# cansat_vehicle_v3_brd2.net
KiCad netlist of a schematic drawn in EAGLE
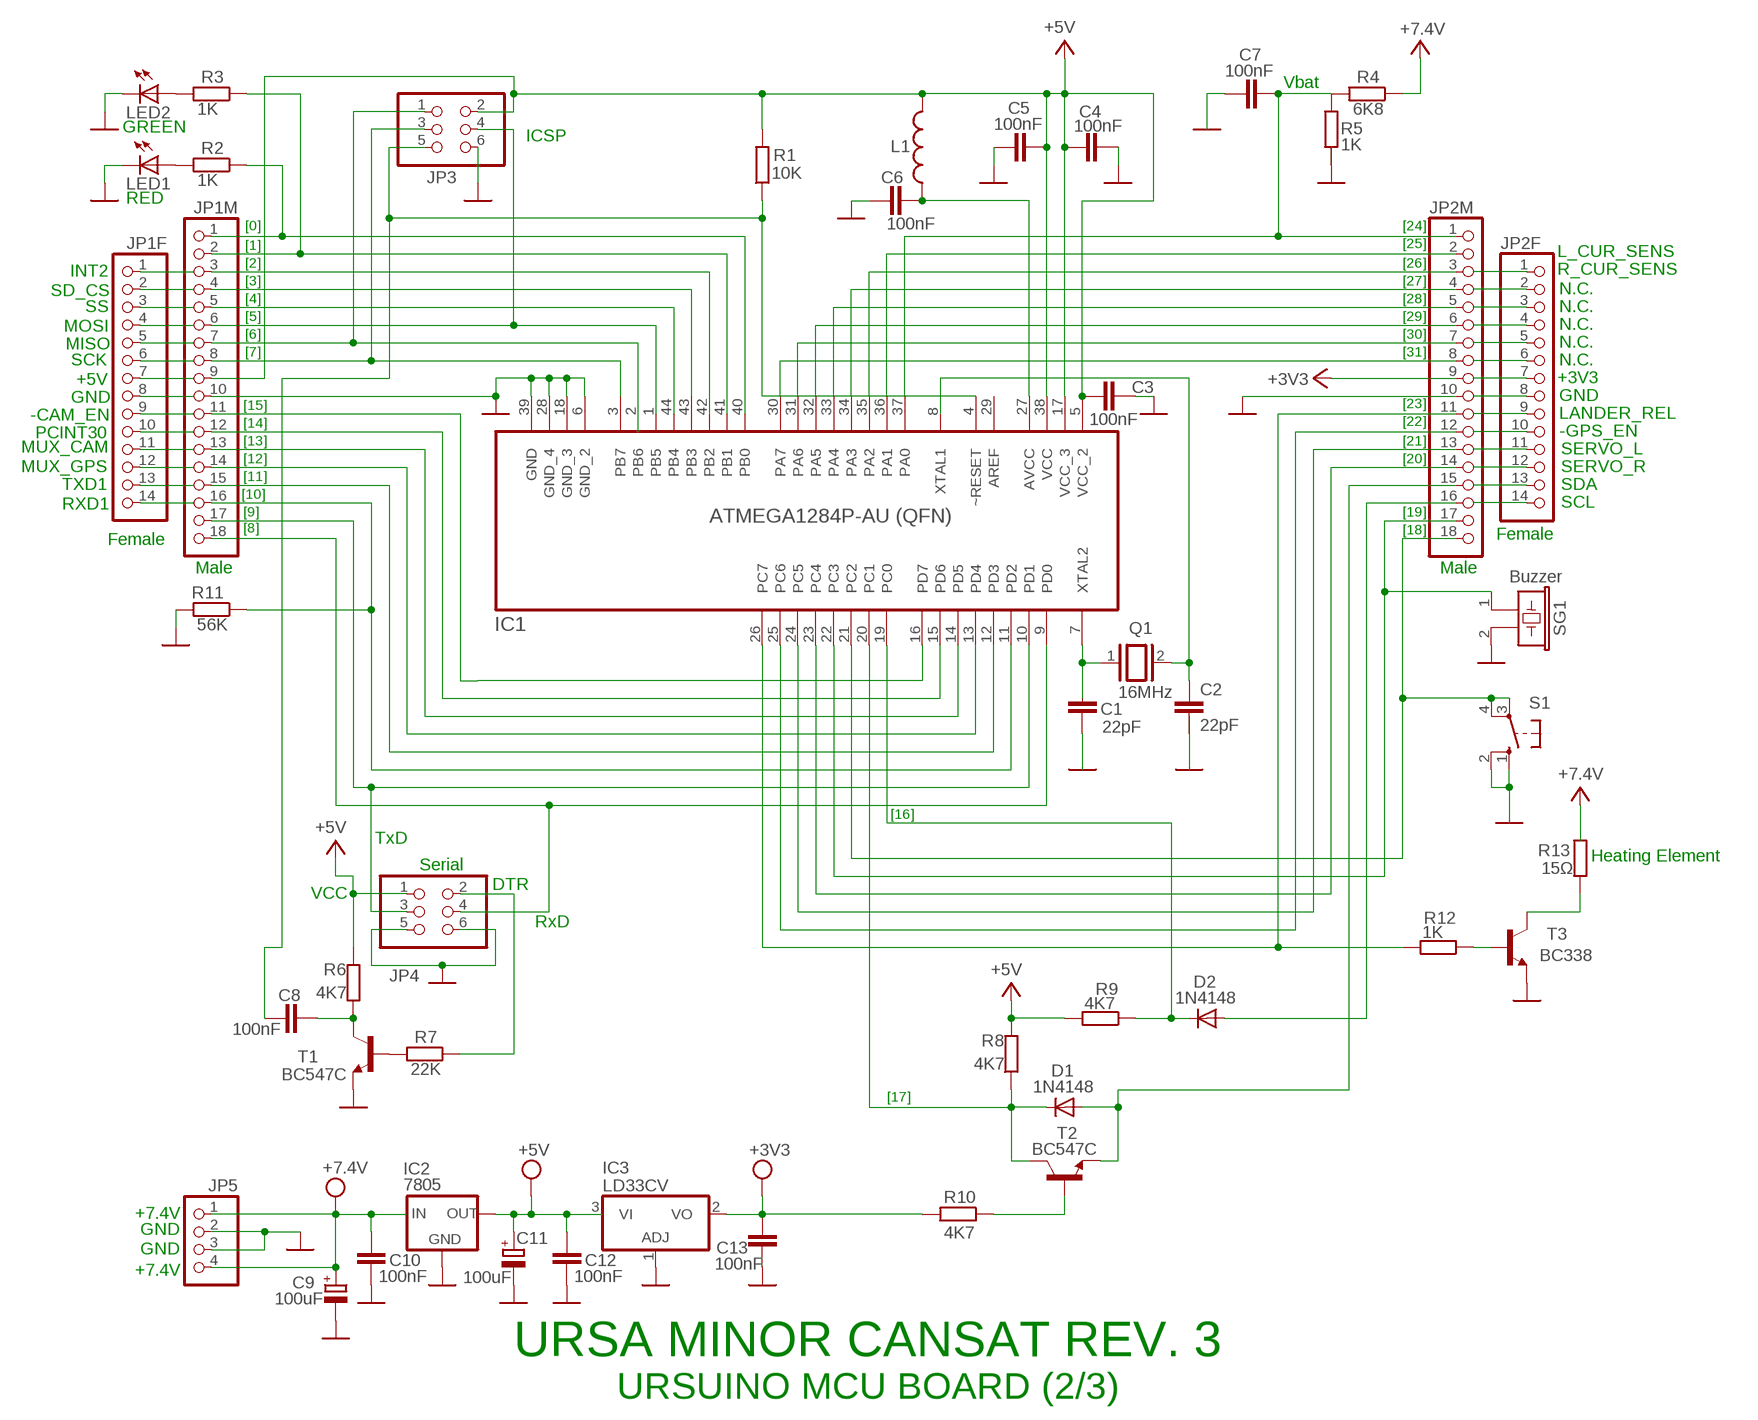
[diagram p0: schematic, sheet 1]

(export (version "E")
  (design (tool "Eeschema 10.0.6"))
  (components
    (comp (ref "C1")
      (value "22pF")
      (footprint "eagle-import:C2.5-2")
      (libsource (lib "eagle-import") (part "C2.5/2"))
    )
    (comp (ref "C2")
      (value "22pF")
      (footprint "eagle-import:C2.5-2")
      (libsource (lib "eagle-import") (part "C2.5/2"))
    )
    (comp (ref "C3")
      (value "100nF")
      (footprint "eagle-import:C2.5-2")
      (libsource (lib "eagle-import") (part "C2.5/2"))
    )
    (comp (ref "C4")
      (value "100nF")
      (footprint "eagle-import:C2.5-2")
      (libsource (lib "eagle-import") (part "C2.5/2"))
    )
    (comp (ref "C5")
      (value "100nF")
      (footprint "eagle-import:C2.5-2")
      (libsource (lib "eagle-import") (part "C2.5/2"))
    )
    (comp (ref "C6")
      (value "100nF")
      (footprint "eagle-import:C2.5-2")
      (libsource (lib "eagle-import") (part "C2.5/2"))
    )
    (comp (ref "C7")
      (value "100nF")
      (footprint "eagle-import:C2.5-2")
      (libsource (lib "eagle-import") (part "C2.5/2"))
    )
    (comp (ref "C8")
      (value "100nF")
      (footprint "eagle-import:C2.5-2")
      (libsource (lib "eagle-import") (part "C2.5/2"))
    )
    (comp (ref "C9")
      (value "100uF")
      (footprint "eagle-import:E2,5-7")
      (libsource (lib "eagle-import") (part "CPOL-EUE2.5-7"))
    )
    (comp (ref "C10")
      (value "100nF")
      (footprint "eagle-import:C2.5-2")
      (libsource (lib "eagle-import") (part "C2.5/2"))
    )
    (comp (ref "C11")
      (value "100uF")
      (footprint "eagle-import:E2,5-7")
      (libsource (lib "eagle-import") (part "CPOL-EUE2.5-7"))
    )
    (comp (ref "C12")
      (value "100nF")
      (footprint "eagle-import:C2.5-2")
      (libsource (lib "eagle-import") (part "C2.5/2"))
    )
    (comp (ref "C13")
      (value "100nF")
      (footprint "eagle-import:C2.5-2")
      (libsource (lib "eagle-import") (part "C2.5/2"))
    )
    (comp (ref "D1")
      (value "1N4148")
      (footprint "eagle-import:DO35-10")
      (libsource (lib "eagle-import") (part "1N4148DO35-10"))
    )
    (comp (ref "D2")
      (value "1N4148")
      (footprint "eagle-import:DO35-10")
      (libsource (lib "eagle-import") (part "1N4148DO35-10"))
    )
    (comp (ref "IC1")
      (value "ATMEGA1284P-AU (QFN)")
      (footprint "eagle-import:QFP80P1200X1200X120-44N")
      (fields (field (name "MPN") "ATMEGA1284P-AU"))
      (libsource (lib "eagle-import") (part "ATMEGA1284P-AU"))
    )
    (comp (ref "IC2")
      (value "7805")
      (footprint "eagle-import:78XXL")
      (libsource (lib "eagle-import") (part "78XXL"))
    )
    (comp (ref "IC3")
      (value "LD33CV")
      (footprint "eagle-import:TO220H")
      (libsource (lib "eagle-import") (part "317T"))
    )
    (comp (ref "JP1F")
      (value "PINHD-1X14")
      (footprint "eagle-import:1X14")
      (libsource (lib "eagle-import") (part "PINHD-1X14"))
    )
    (comp (ref "JP1M")
      (value "PINHD-1X18")
      (footprint "eagle-import:1X18")
      (libsource (lib "eagle-import") (part "PINHD-1X18"))
    )
    (comp (ref "JP2F")
      (value "PINHD-1X14")
      (footprint "eagle-import:1X14")
      (libsource (lib "eagle-import") (part "PINHD-1X14"))
    )
    (comp (ref "JP2M")
      (value "PINHD-1X18")
      (footprint "eagle-import:1X18")
      (libsource (lib "eagle-import") (part "PINHD-1X18"))
    )
    (comp (ref "JP3")
      (value "PINHD-2X3")
      (footprint "eagle-import:2X03")
      (libsource (lib "eagle-import") (part "PINHD-2X3"))
    )
    (comp (ref "JP4")
      (value "PINHD-2X3")
      (footprint "eagle-import:2X03")
      (libsource (lib "eagle-import") (part "PINHD-2X3"))
    )
    (comp (ref "JP5")
      (value "PINHD-1X4")
      (footprint "eagle-import:1X04")
      (libsource (lib "eagle-import") (part "PINHD-1X4"))
    )
    (comp (ref "L1")
      (value "L-US0204/5")
      (footprint "eagle-import:0204_5")
      (libsource (lib "eagle-import") (part "L-US0204/5"))
    )
    (comp (ref "LED1")
      (value "LED3MM")
      (footprint "eagle-import:LED3MM")
      (libsource (lib "eagle-import") (part "LED3MM"))
    )
    (comp (ref "LED2")
      (value "LED3MM")
      (footprint "eagle-import:LED3MM")
      (libsource (lib "eagle-import") (part "LED3MM"))
    )
    (comp (ref "Q1")
      (value "16MHz")
      (footprint "eagle-import:Q")
      (libsource (lib "eagle-import") (part "XTAL"))
    )
    (comp (ref "R1")
      (value "10K")
      (footprint "eagle-import:0204V")
      (libsource (lib "eagle-import") (part "R-EU_0204_2V"))
    )
    (comp (ref "R2")
      (value "1K")
      (footprint "eagle-import:0204V")
      (libsource (lib "eagle-import") (part "R-EU_0204_2V"))
    )
    (comp (ref "R3")
      (value "1K")
      (footprint "eagle-import:0204V")
      (libsource (lib "eagle-import") (part "R-EU_0204_2V"))
    )
    (comp (ref "R4")
      (value "6K8")
      (footprint "eagle-import:0204V")
      (libsource (lib "eagle-import") (part "R-EU_0204_2V"))
    )
    (comp (ref "R5")
      (value "1K")
      (footprint "eagle-import:0204V")
      (libsource (lib "eagle-import") (part "R-EU_0204_2V"))
    )
    (comp (ref "R6")
      (value "4K7")
      (footprint "eagle-import:0204V")
      (libsource (lib "eagle-import") (part "R-EU_0204_2V"))
    )
    (comp (ref "R7")
      (value "22K")
      (footprint "eagle-import:0204V")
      (libsource (lib "eagle-import") (part "R-EU_0204_2V"))
    )
    (comp (ref "R8")
      (value "4K7")
      (footprint "eagle-import:0204V")
      (libsource (lib "eagle-import") (part "R-EU_0204_2V"))
    )
    (comp (ref "R9")
      (value "4K7")
      (footprint "eagle-import:0204V")
      (libsource (lib "eagle-import") (part "R-EU_0204_2V"))
    )
    (comp (ref "R10")
      (value "4K7")
      (footprint "eagle-import:0204V")
      (libsource (lib "eagle-import") (part "R-EU_0204_2V"))
    )
    (comp (ref "R11")
      (value "56K")
      (footprint "eagle-import:0204V")
      (libsource (lib "eagle-import") (part "R-EU_0204_2V"))
    )
    (comp (ref "R12")
      (value "1K")
      (footprint "eagle-import:0204V")
      (libsource (lib "eagle-import") (part "R-EU_0204_2V"))
    )
    (comp (ref "R13")
      (value "15Ω")
      (footprint "eagle-import:0204V")
      (libsource (lib "eagle-import") (part "R-EU_0204_2V"))
    )
    (comp (ref "S1")
      (value "10-XX")
      (footprint "eagle-import:B3F-10XX")
      (fields (field (name "MPN") "B3F-1000"))
      (libsource (lib "eagle-import") (part "10-XX"))
    )
    (comp (ref "SG1")
      (value "Buzzer")
      (footprint "eagle-import:B_C11L")
      (libsource (lib "eagle-import") (part "B/C11L"))
    )
    (comp (ref "T1")
      (value "BC547C")
      (footprint "eagle-import:TO92-CBE")
      (libsource (lib "eagle-import") (part "-NPN-TO92-CBEBC547B"))
    )
    (comp (ref "T2")
      (value "BC547C")
      (footprint "eagle-import:TO92-CBE")
      (libsource (lib "eagle-import") (part "-NPN-TO92-CBEBC547B"))
    )
    (comp (ref "T3")
      (value "BC338")
      (footprint "eagle-import:TO92-CBE")
      (libsource (lib "eagle-import") (part "-NPN-TO92-CBEBC547B"))
    )
  )
  (nets
    (net (code "1") (name "+3V3") (class "Default")
      (node (ref "C10") (pin "1") (pinfunction "1_1") (pintype "passive"))
      (node (ref "C11") (pin "+") (pinfunction "+_+") (pintype "passive"))
      (node (ref "C12") (pin "1") (pinfunction "1_1") (pintype "passive"))
      (node (ref "C13") (pin "1") (pinfunction "1_1") (pintype "passive"))
      (node (ref "C3") (pin "1") (pinfunction "1_1") (pintype "passive"))
      (node (ref "C4") (pin "2") (pinfunction "2_2") (pintype "passive"))
      (node (ref "C5") (pin "1") (pinfunction "1_1") (pintype "passive"))
      (node (ref "C9") (pin "+") (pinfunction "+_+") (pintype "passive"))
      (node (ref "IC1") (pin "17") (pinfunction "VCC_3_17") (pintype "power_in"))
      (node (ref "IC1") (pin "38") (pinfunction "VCC_38") (pintype "power_in"))
      (node (ref "IC1") (pin "5") (pinfunction "VCC_2_5") (pintype "power_in"))
      (node (ref "IC2") (pin "IN") (pinfunction "IN_IN") (pintype "input"))
      (node (ref "IC2") (pin "OUT") (pinfunction "OUT_OUT") (pintype "passive"))
      (node (ref "IC3") (pin "2") (pinfunction "VO_2") (pintype "passive"))
      (node (ref "IC3") (pin "3") (pinfunction "VI_3") (pintype "input"))
      (node (ref "JP1M") (pin "9") (pinfunction "9_9") (pintype "passive"))
      (node (ref "JP2M") (pin "9") (pinfunction "9_9") (pintype "passive"))
      (node (ref "JP3") (pin "2") (pinfunction "2_2") (pintype "passive"))
      (node (ref "JP4") (pin "1") (pinfunction "1_1") (pintype "passive"))
      (node (ref "JP5") (pin "1") (pinfunction "1_1") (pintype "passive"))
      (node (ref "JP5") (pin "4") (pinfunction "4_4") (pintype "passive"))
      (node (ref "L1") (pin "2") (pinfunction "2_2") (pintype "passive"))
      (node (ref "R1") (pin "2") (pinfunction "2_2") (pintype "passive"))
      (node (ref "R10") (pin "2") (pinfunction "2_2") (pintype "passive"))
      (node (ref "R4") (pin "1") (pinfunction "1_1") (pintype "passive"))
      (node (ref "R6") (pin "2") (pinfunction "2_2") (pintype "passive"))
      (node (ref "R8") (pin "2") (pinfunction "2_2") (pintype "passive"))
      (node (ref "R9") (pin "2") (pinfunction "2_2") (pintype "passive"))
    )
    (net (code "2") (name "GND") (class "Default")
      (node (ref "C1") (pin "2") (pinfunction "2_2") (pintype "passive"))
      (node (ref "C10") (pin "2") (pinfunction "2_2") (pintype "passive"))
      (node (ref "C11") (pin "-") (pinfunction "-_-") (pintype "passive"))
      (node (ref "C12") (pin "2") (pinfunction "2_2") (pintype "passive"))
      (node (ref "C13") (pin "2") (pinfunction "2_2") (pintype "passive"))
      (node (ref "C2") (pin "2") (pinfunction "2_2") (pintype "passive"))
      (node (ref "C3") (pin "2") (pinfunction "2_2") (pintype "passive"))
      (node (ref "C4") (pin "1") (pinfunction "1_1") (pintype "passive"))
      (node (ref "C5") (pin "2") (pinfunction "2_2") (pintype "passive"))
      (node (ref "C6") (pin "1") (pinfunction "1_1") (pintype "passive"))
      (node (ref "C9") (pin "-") (pinfunction "-_-") (pintype "passive"))
      (node (ref "IC1") (pin "18") (pinfunction "GND_3_18") (pintype "passive"))
      (node (ref "IC1") (pin "28") (pinfunction "GND_4_28") (pintype "passive"))
      (node (ref "IC1") (pin "39") (pinfunction "GND_39") (pintype "passive"))
      (node (ref "IC1") (pin "6") (pinfunction "GND_2_6") (pintype "passive"))
      (node (ref "IC2") (pin "GND") (pinfunction "GND_GND") (pintype "input"))
      (node (ref "IC3") (pin "1") (pinfunction "ADJ_1") (pintype "input"))
      (node (ref "JP1M") (pin "10") (pinfunction "10_10") (pintype "passive"))
      (node (ref "JP2M") (pin "10") (pinfunction "10_10") (pintype "passive"))
      (node (ref "JP3") (pin "6") (pinfunction "6_6") (pintype "passive"))
      (node (ref "JP4") (pin "5") (pinfunction "5_5") (pintype "passive"))
      (node (ref "JP4") (pin "6") (pinfunction "6_6") (pintype "passive"))
      (node (ref "JP5") (pin "2") (pinfunction "2_2") (pintype "passive"))
      (node (ref "JP5") (pin "3") (pinfunction "3_3") (pintype "passive"))
      (node (ref "LED1") (pin "K") (pinfunction "C_K") (pintype "passive"))
      (node (ref "LED2") (pin "K") (pinfunction "C_K") (pintype "passive"))
      (node (ref "R11") (pin "2") (pinfunction "2_2") (pintype "passive"))
      (node (ref "R5") (pin "1") (pinfunction "1_1") (pintype "passive"))
      (node (ref "SG1") (pin "2") (pinfunction "2_2") (pintype "passive"))
      (node (ref "T1") (pin "E") (pinfunction "E_E") (pintype "passive"))
      (node (ref "T3") (pin "E") (pinfunction "E_E") (pintype "passive"))
    )
    (net (code "3") (name "Net-(C8-Pad2)") (class "Default")
      (node (ref "C8") (pin "2") (pinfunction "2_2") (pintype "passive"))
      (node (ref "R6") (pin "1") (pinfunction "1_1") (pintype "passive"))
      (node (ref "T1") (pin "C") (pinfunction "C_C") (pintype "passive"))
    )
    (net (code "4") (name "Net-(D1-PadA)") (class "Default")
      (node (ref "D1") (pin "A") (pinfunction "A_A") (pintype "passive"))
      (node (ref "JP2M") (pin "15") (pinfunction "15_15") (pintype "passive"))
      (node (ref "T2") (pin "E") (pinfunction "E_E") (pintype "passive"))
    )
    (net (code "5") (name "Net-(D2-PadA)") (class "Default")
      (node (ref "D2") (pin "A") (pinfunction "A_A") (pintype "passive"))
      (node (ref "JP2M") (pin "16") (pinfunction "16_16") (pintype "passive"))
    )
    (net (code "6") (name "Net-(IC1-AVCC)") (class "Default")
      (node (ref "C6") (pin "2") (pinfunction "2_2") (pintype "passive"))
      (node (ref "IC1") (pin "27") (pinfunction "AVCC_27") (pintype "power_in"))
      (node (ref "L1") (pin "1") (pinfunction "1_1") (pintype "passive"))
    )
    (net (code "7") (name "Net-(IC1-PA0)") (class "Default")
      (node (ref "C7") (pin "1") (pinfunction "1_1") (pintype "passive"))
      (node (ref "IC1") (pin "37") (pinfunction "PA0_37") (pintype "bidirectional"))
      (node (ref "JP2M") (pin "1") (pinfunction "1_1") (pintype "passive"))
      (node (ref "R4") (pin "2") (pinfunction "2_2") (pintype "passive"))
      (node (ref "R5") (pin "2") (pinfunction "2_2") (pintype "passive"))
    )
    (net (code "8") (name "Net-(IC1-PA1)") (class "Default")
      (node (ref "IC1") (pin "36") (pinfunction "PA1_36") (pintype "bidirectional"))
      (node (ref "JP2M") (pin "2") (pinfunction "2_2") (pintype "passive"))
    )
    (net (code "9") (name "Net-(IC1-PA2)") (class "Default")
      (node (ref "IC1") (pin "35") (pinfunction "PA2_35") (pintype "bidirectional"))
      (node (ref "JP2M") (pin "3") (pinfunction "3_3") (pintype "passive"))
    )
    (net (code "10") (name "Net-(IC1-PA3)") (class "Default")
      (node (ref "IC1") (pin "34") (pinfunction "PA3_34") (pintype "bidirectional"))
      (node (ref "JP2M") (pin "4") (pinfunction "4_4") (pintype "passive"))
    )
    (net (code "11") (name "Net-(IC1-PA4)") (class "Default")
      (node (ref "IC1") (pin "33") (pinfunction "PA4_33") (pintype "bidirectional"))
      (node (ref "JP2M") (pin "5") (pinfunction "5_5") (pintype "passive"))
    )
    (net (code "12") (name "Net-(IC1-PA5)") (class "Default")
      (node (ref "IC1") (pin "32") (pinfunction "PA5_32") (pintype "bidirectional"))
      (node (ref "JP2M") (pin "6") (pinfunction "6_6") (pintype "passive"))
    )
    (net (code "13") (name "Net-(IC1-PA6)") (class "Default")
      (node (ref "IC1") (pin "31") (pinfunction "PA6_31") (pintype "bidirectional"))
      (node (ref "JP2M") (pin "7") (pinfunction "7_7") (pintype "passive"))
    )
    (net (code "14") (name "Net-(IC1-PA7)") (class "Default")
      (node (ref "IC1") (pin "30") (pinfunction "PA7_30") (pintype "bidirectional"))
      (node (ref "JP2M") (pin "8") (pinfunction "8_8") (pintype "passive"))
    )
    (net (code "15") (name "Net-(IC1-PB0)") (class "Default")
      (node (ref "IC1") (pin "40") (pinfunction "PB0_40") (pintype "bidirectional"))
      (node (ref "JP1M") (pin "1") (pinfunction "1_1") (pintype "passive"))
      (node (ref "R2") (pin "1") (pinfunction "1_1") (pintype "passive"))
    )
    (net (code "16") (name "Net-(IC1-PB1)") (class "Default")
      (node (ref "IC1") (pin "41") (pinfunction "PB1_41") (pintype "bidirectional"))
      (node (ref "JP1M") (pin "2") (pinfunction "2_2") (pintype "passive"))
      (node (ref "R3") (pin "1") (pinfunction "1_1") (pintype "passive"))
    )
    (net (code "17") (name "Net-(IC1-PB2)") (class "Default")
      (node (ref "IC1") (pin "42") (pinfunction "PB2_42") (pintype "bidirectional"))
      (node (ref "JP1M") (pin "3") (pinfunction "3_3") (pintype "passive"))
    )
    (net (code "18") (name "Net-(IC1-PB3)") (class "Default")
      (node (ref "IC1") (pin "43") (pinfunction "PB3_43") (pintype "bidirectional"))
      (node (ref "JP1M") (pin "4") (pinfunction "4_4") (pintype "passive"))
    )
    (net (code "19") (name "Net-(IC1-PB4)") (class "Default")
      (node (ref "IC1") (pin "44") (pinfunction "PB4_44") (pintype "bidirectional"))
      (node (ref "JP1M") (pin "5") (pinfunction "5_5") (pintype "passive"))
    )
    (net (code "20") (name "Net-(IC1-PB5)") (class "Default")
      (node (ref "IC1") (pin "1") (pinfunction "PB5_1") (pintype "bidirectional"))
      (node (ref "JP1M") (pin "6") (pinfunction "6_6") (pintype "passive"))
      (node (ref "JP3") (pin "4") (pinfunction "4_4") (pintype "passive"))
    )
    (net (code "21") (name "Net-(IC1-PB6)") (class "Default")
      (node (ref "IC1") (pin "2") (pinfunction "PB6_2") (pintype "bidirectional"))
      (node (ref "JP1M") (pin "7") (pinfunction "7_7") (pintype "passive"))
      (node (ref "JP3") (pin "1") (pinfunction "1_1") (pintype "passive"))
    )
    (net (code "22") (name "Net-(IC1-PB7)") (class "Default")
      (node (ref "IC1") (pin "3") (pinfunction "PB7_3") (pintype "bidirectional"))
      (node (ref "JP1M") (pin "8") (pinfunction "8_8") (pintype "passive"))
      (node (ref "JP3") (pin "3") (pinfunction "3_3") (pintype "passive"))
    )
    (net (code "23") (name "Net-(IC1-PC0)") (class "Default")
      (node (ref "D2") (pin "C") (pinfunction "C_C") (pintype "passive"))
      (node (ref "IC1") (pin "19") (pinfunction "PC0_19") (pintype "bidirectional"))
      (node (ref "R9") (pin "1") (pinfunction "1_1") (pintype "passive"))
    )
    (net (code "24") (name "Net-(IC1-PC1)") (class "Default")
      (node (ref "D1") (pin "C") (pinfunction "C_C") (pintype "passive"))
      (node (ref "IC1") (pin "20") (pinfunction "PC1_20") (pintype "bidirectional"))
      (node (ref "R8") (pin "1") (pinfunction "1_1") (pintype "passive"))
      (node (ref "T2") (pin "C") (pinfunction "C_C") (pintype "passive"))
    )
    (net (code "25") (name "Net-(IC1-PC2)") (class "Default")
      (node (ref "IC1") (pin "21") (pinfunction "PC2_21") (pintype "bidirectional"))
      (node (ref "JP2M") (pin "18") (pinfunction "18_18") (pintype "passive"))
      (node (ref "S1") (pin "3") (pinfunction "P_3") (pintype "passive"))
      (node (ref "S1") (pin "4") (pinfunction "P1_4") (pintype "passive"))
    )
    (net (code "26") (name "Net-(IC1-PC3)") (class "Default")
      (node (ref "IC1") (pin "22") (pinfunction "PC3_22") (pintype "bidirectional"))
      (node (ref "JP2M") (pin "17") (pinfunction "17_17") (pintype "passive"))
      (node (ref "SG1") (pin "1") (pinfunction "1_1") (pintype "passive"))
    )
    (net (code "27") (name "Net-(IC1-PC4)") (class "Default")
      (node (ref "IC1") (pin "23") (pinfunction "PC4_23") (pintype "bidirectional"))
      (node (ref "JP2M") (pin "14") (pinfunction "14_14") (pintype "passive"))
    )
    (net (code "28") (name "Net-(IC1-PC5)") (class "Default")
      (node (ref "IC1") (pin "24") (pinfunction "PC5_24") (pintype "bidirectional"))
      (node (ref "JP2M") (pin "13") (pinfunction "13_13") (pintype "passive"))
    )
    (net (code "29") (name "Net-(IC1-PC6)") (class "Default")
      (node (ref "IC1") (pin "25") (pinfunction "PC6_25") (pintype "bidirectional"))
      (node (ref "JP2M") (pin "12") (pinfunction "12_12") (pintype "passive"))
    )
    (net (code "30") (name "Net-(IC1-PC7)") (class "Default")
      (node (ref "IC1") (pin "26") (pinfunction "PC7_26") (pintype "bidirectional"))
      (node (ref "JP2M") (pin "11") (pinfunction "11_11") (pintype "passive"))
      (node (ref "R12") (pin "2") (pinfunction "2_2") (pintype "passive"))
    )
    (net (code "31") (name "Net-(IC1-PD0)") (class "Default")
      (node (ref "IC1") (pin "9") (pinfunction "PD0_9") (pintype "bidirectional"))
      (node (ref "JP1M") (pin "18") (pinfunction "18_18") (pintype "passive"))
      (node (ref "JP4") (pin "4") (pinfunction "4_4") (pintype "passive"))
    )
    (net (code "32") (name "Net-(IC1-PD1)") (class "Default")
      (node (ref "IC1") (pin "10") (pinfunction "PD1_10") (pintype "bidirectional"))
      (node (ref "JP1M") (pin "17") (pinfunction "17_17") (pintype "passive"))
      (node (ref "JP4") (pin "3") (pinfunction "3_3") (pintype "passive"))
    )
    (net (code "33") (name "Net-(IC1-PD2)") (class "Default")
      (node (ref "IC1") (pin "11") (pinfunction "PD2_11") (pintype "bidirectional"))
      (node (ref "JP1M") (pin "16") (pinfunction "16_16") (pintype "passive"))
      (node (ref "R11") (pin "1") (pinfunction "1_1") (pintype "passive"))
    )
    (net (code "34") (name "Net-(IC1-PD3)") (class "Default")
      (node (ref "IC1") (pin "12") (pinfunction "PD3_12") (pintype "bidirectional"))
      (node (ref "JP1M") (pin "15") (pinfunction "15_15") (pintype "passive"))
    )
    (net (code "35") (name "Net-(IC1-PD4)") (class "Default")
      (node (ref "IC1") (pin "13") (pinfunction "PD4_13") (pintype "bidirectional"))
      (node (ref "JP1M") (pin "14") (pinfunction "14_14") (pintype "passive"))
    )
    (net (code "36") (name "Net-(IC1-PD5)") (class "Default")
      (node (ref "IC1") (pin "14") (pinfunction "PD5_14") (pintype "bidirectional"))
      (node (ref "JP1M") (pin "13") (pinfunction "13_13") (pintype "passive"))
    )
    (net (code "37") (name "Net-(IC1-PD6)") (class "Default")
      (node (ref "IC1") (pin "15") (pinfunction "PD6_15") (pintype "bidirectional"))
      (node (ref "JP1M") (pin "12") (pinfunction "12_12") (pintype "passive"))
    )
    (net (code "38") (name "Net-(IC1-PD7)") (class "Default")
      (node (ref "IC1") (pin "16") (pinfunction "PD7_16") (pintype "bidirectional"))
      (node (ref "JP1M") (pin "11") (pinfunction "11_11") (pintype "passive"))
    )
    (net (code "39") (name "Net-(IC1-XTAL1)") (class "Default")
      (node (ref "C2") (pin "1") (pinfunction "1_1") (pintype "passive"))
      (node (ref "IC1") (pin "8") (pinfunction "XTAL1_8") (pintype "input"))
      (node (ref "Q1") (pin "2") (pinfunction "2_2") (pintype "passive"))
    )
    (net (code "40") (name "Net-(IC1-XTAL2)") (class "Default")
      (node (ref "C1") (pin "1") (pinfunction "1_1") (pintype "passive"))
      (node (ref "IC1") (pin "7") (pinfunction "XTAL2_7") (pintype "output"))
      (node (ref "Q1") (pin "1") (pinfunction "1_1") (pintype "passive"))
    )
    (net (code "41") (name "Net-(IC1-~{RESET})") (class "Default")
      (node (ref "C8") (pin "1") (pinfunction "1_1") (pintype "passive"))
      (node (ref "IC1") (pin "4") (pinfunction "~{RESET}_4") (pintype "input"))
      (node (ref "JP3") (pin "5") (pinfunction "5_5") (pintype "passive"))
      (node (ref "R1") (pin "1") (pinfunction "1_1") (pintype "passive"))
    )
    (net (code "42") (name "Net-(JP4-Pad2)") (class "Default")
      (node (ref "JP4") (pin "2") (pinfunction "2_2") (pintype "passive"))
      (node (ref "R7") (pin "1") (pinfunction "1_1") (pintype "passive"))
    )
    (net (code "43") (name "Net-(LED1-PadA)") (class "Default")
      (node (ref "LED1") (pin "A") (pinfunction "A_A") (pintype "passive"))
      (node (ref "R2") (pin "2") (pinfunction "2_2") (pintype "passive"))
    )
    (net (code "44") (name "Net-(LED2-PadA)") (class "Default")
      (node (ref "LED2") (pin "A") (pinfunction "A_A") (pintype "passive"))
      (node (ref "R3") (pin "2") (pinfunction "2_2") (pintype "passive"))
    )
    (net (code "45") (name "Net-(R7-Pad2)") (class "Default")
      (node (ref "R7") (pin "2") (pinfunction "2_2") (pintype "passive"))
      (node (ref "T1") (pin "B") (pinfunction "B_B") (pintype "passive"))
    )
    (net (code "46") (name "Net-(R10-Pad1)") (class "Default")
      (node (ref "R10") (pin "1") (pinfunction "1_1") (pintype "passive"))
      (node (ref "T2") (pin "B") (pinfunction "B_B") (pintype "passive"))
    )
    (net (code "47") (name "Net-(R12-Pad1)") (class "Default")
      (node (ref "R12") (pin "1") (pinfunction "1_1") (pintype "passive"))
      (node (ref "T3") (pin "B") (pinfunction "B_B") (pintype "passive"))
    )
    (net (code "48") (name "Net-(R13-Pad1)") (class "Default")
      (node (ref "R13") (pin "1") (pinfunction "1_1") (pintype "passive"))
      (node (ref "T3") (pin "C") (pinfunction "C_C") (pintype "passive"))
    )
    (net (code "49") (name "Net-(S1-S)") (class "Default")
      (node (ref "S1") (pin "1") (pinfunction "S_1") (pintype "passive"))
      (node (ref "S1") (pin "2") (pinfunction "S1_2") (pintype "passive"))
    )
    (net (code "50") (name "unconnected-(C7-Pad2)") (class "Default")
      (node (ref "C7") (pin "2") (pinfunction "2_2") (pintype "passive"))
    )
    (net (code "51") (name "unconnected-(IC1-AREF-Pad29)") (class "Default")
      (node (ref "IC1") (pin "29") (pinfunction "AREF_29") (pintype "input"))
    )
    (net (code "52") (name "unconnected-(JP1F-Pad1)") (class "Default")
      (node (ref "JP1F") (pin "1") (pinfunction "1_1") (pintype "passive"))
    )
    (net (code "53") (name "unconnected-(JP1F-Pad2)") (class "Default")
      (node (ref "JP1F") (pin "2") (pinfunction "2_2") (pintype "passive"))
    )
    (net (code "54") (name "unconnected-(JP1F-Pad3)") (class "Default")
      (node (ref "JP1F") (pin "3") (pinfunction "3_3") (pintype "passive"))
    )
    (net (code "55") (name "unconnected-(JP1F-Pad4)") (class "Default")
      (node (ref "JP1F") (pin "4") (pinfunction "4_4") (pintype "passive"))
    )
    (net (code "56") (name "unconnected-(JP1F-Pad5)") (class "Default")
      (node (ref "JP1F") (pin "5") (pinfunction "5_5") (pintype "passive"))
    )
    (net (code "57") (name "unconnected-(JP1F-Pad6)") (class "Default")
      (node (ref "JP1F") (pin "6") (pinfunction "6_6") (pintype "passive"))
    )
    (net (code "58") (name "unconnected-(JP1F-Pad7)") (class "Default")
      (node (ref "JP1F") (pin "7") (pinfunction "7_7") (pintype "passive"))
    )
    (net (code "59") (name "unconnected-(JP1F-Pad8)") (class "Default")
      (node (ref "JP1F") (pin "8") (pinfunction "8_8") (pintype "passive"))
    )
    (net (code "60") (name "unconnected-(JP1F-Pad9)") (class "Default")
      (node (ref "JP1F") (pin "9") (pinfunction "9_9") (pintype "passive"))
    )
    (net (code "61") (name "unconnected-(JP1F-Pad10)") (class "Default")
      (node (ref "JP1F") (pin "10") (pinfunction "10_10") (pintype "passive"))
    )
    (net (code "62") (name "unconnected-(JP1F-Pad11)") (class "Default")
      (node (ref "JP1F") (pin "11") (pinfunction "11_11") (pintype "passive"))
    )
    (net (code "63") (name "unconnected-(JP1F-Pad12)") (class "Default")
      (node (ref "JP1F") (pin "12") (pinfunction "12_12") (pintype "passive"))
    )
    (net (code "64") (name "unconnected-(JP1F-Pad13)") (class "Default")
      (node (ref "JP1F") (pin "13") (pinfunction "13_13") (pintype "passive"))
    )
    (net (code "65") (name "unconnected-(JP1F-Pad14)") (class "Default")
      (node (ref "JP1F") (pin "14") (pinfunction "14_14") (pintype "passive"))
    )
    (net (code "66") (name "unconnected-(JP2F-Pad1)") (class "Default")
      (node (ref "JP2F") (pin "1") (pinfunction "1_1") (pintype "passive"))
    )
    (net (code "67") (name "unconnected-(JP2F-Pad2)") (class "Default")
      (node (ref "JP2F") (pin "2") (pinfunction "2_2") (pintype "passive"))
    )
    (net (code "68") (name "unconnected-(JP2F-Pad3)") (class "Default")
      (node (ref "JP2F") (pin "3") (pinfunction "3_3") (pintype "passive"))
    )
    (net (code "69") (name "unconnected-(JP2F-Pad4)") (class "Default")
      (node (ref "JP2F") (pin "4") (pinfunction "4_4") (pintype "passive"))
    )
    (net (code "70") (name "unconnected-(JP2F-Pad5)") (class "Default")
      (node (ref "JP2F") (pin "5") (pinfunction "5_5") (pintype "passive"))
    )
    (net (code "71") (name "unconnected-(JP2F-Pad6)") (class "Default")
      (node (ref "JP2F") (pin "6") (pinfunction "6_6") (pintype "passive"))
    )
    (net (code "72") (name "unconnected-(JP2F-Pad7)") (class "Default")
      (node (ref "JP2F") (pin "7") (pinfunction "7_7") (pintype "passive"))
    )
    (net (code "73") (name "unconnected-(JP2F-Pad8)") (class "Default")
      (node (ref "JP2F") (pin "8") (pinfunction "8_8") (pintype "passive"))
    )
    (net (code "74") (name "unconnected-(JP2F-Pad9)") (class "Default")
      (node (ref "JP2F") (pin "9") (pinfunction "9_9") (pintype "passive"))
    )
    (net (code "75") (name "unconnected-(JP2F-Pad10)") (class "Default")
      (node (ref "JP2F") (pin "10") (pinfunction "10_10") (pintype "passive"))
    )
    (net (code "76") (name "unconnected-(JP2F-Pad11)") (class "Default")
      (node (ref "JP2F") (pin "11") (pinfunction "11_11") (pintype "passive"))
    )
    (net (code "77") (name "unconnected-(JP2F-Pad12)") (class "Default")
      (node (ref "JP2F") (pin "12") (pinfunction "12_12") (pintype "passive"))
    )
    (net (code "78") (name "unconnected-(JP2F-Pad13)") (class "Default")
      (node (ref "JP2F") (pin "13") (pinfunction "13_13") (pintype "passive"))
    )
    (net (code "79") (name "unconnected-(JP2F-Pad14)") (class "Default")
      (node (ref "JP2F") (pin "14") (pinfunction "14_14") (pintype "passive"))
    )
    (net (code "80") (name "unconnected-(R13-Pad2)") (class "Default")
      (node (ref "R13") (pin "2") (pinfunction "2_2") (pintype "passive"))
    )
  )
)
